# Node_PCB_v20234.net
KiCad netlist of a schematic drawn in EAGLE
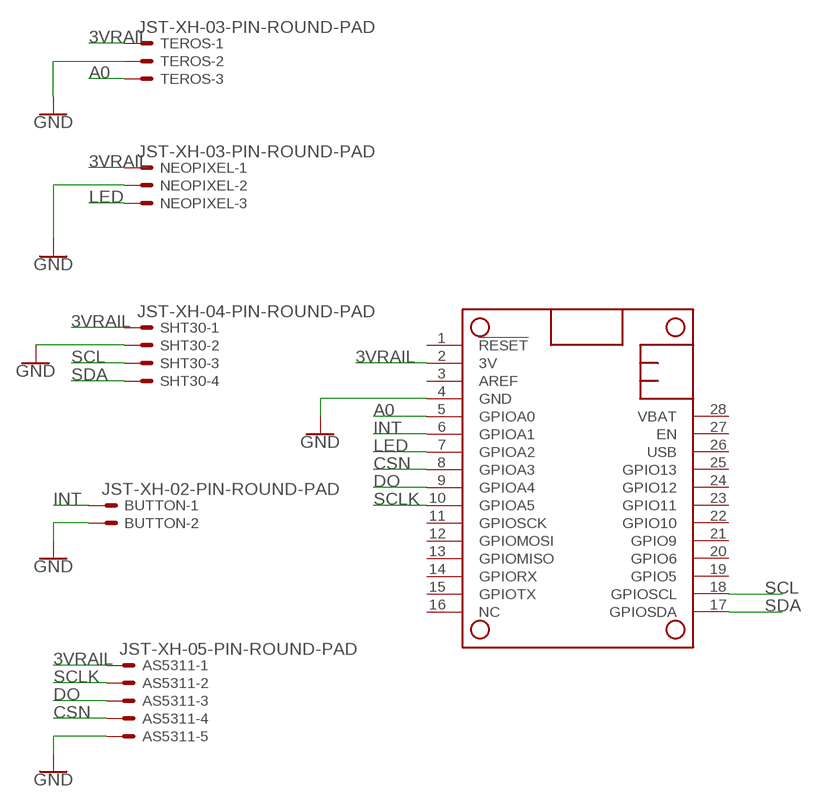
[diagram p0: schematic, sheet 1]

(export (version "E")
  (design (tool "Eeschema 10.0.6"))
  (components
    (comp (ref "AS5311")
      (value "JST-XH-05-PIN-ROUND-PAD")
      (footprint "eagle-import:JST-XH-05-PACKAGE-ROUND-PAD")
      (libsource (lib "eagle-import") (part "JST-XH-05-PIN-ROUND-PAD"))
    )
    (comp (ref "BUTTON")
      (value "JST-XH-02-PIN-ROUND-PAD")
      (footprint "eagle-import:JST-XH-02-PACKAGE-ROUND-PAD")
      (libsource (lib "eagle-import") (part "JST-XH-02-PIN-ROUND-PAD"))
    )
    (comp (ref "MS1")
      (value "FEATHERWING")
      (footprint "eagle-import:FEATHERWING")
      (libsource (lib "eagle-import") (part "FEATHERWING"))
    )
    (comp (ref "NEOPIXEL")
      (value "JST-XH-03-PIN-ROUND-PAD")
      (footprint "eagle-import:JST-XH-03-PACKAGE-ROUND-PAD")
      (libsource (lib "eagle-import") (part "JST-XH-03-PIN-ROUND-PAD"))
    )
    (comp (ref "SHT30")
      (value "JST-XH-04-PIN-ROUND-PAD")
      (footprint "eagle-import:JST-XH-04-PACKAGE-ROUND-PAD")
      (libsource (lib "eagle-import") (part "JST-XH-04-PIN-ROUND-PAD"))
    )
    (comp (ref "TEROS")
      (value "JST-XH-03-PIN-ROUND-PAD")
      (footprint "eagle-import:JST-XH-03-PACKAGE-ROUND-PAD")
      (libsource (lib "eagle-import") (part "JST-XH-03-PIN-ROUND-PAD"))
    )
  )
  (nets
    (net (code "1") (name "/3VRAIL") (class "Default")
      (node (ref "AS5311") (pin "1") (pinfunction "S_1") (pintype "passive"))
      (node (ref "MS1") (pin "2") (pinfunction "3V_2") (pintype "power_in"))
      (node (ref "NEOPIXEL") (pin "1") (pinfunction "S_1") (pintype "passive"))
      (node (ref "SHT30") (pin "1") (pinfunction "S_1") (pintype "passive"))
      (node (ref "TEROS") (pin "1") (pinfunction "S_1") (pintype "passive"))
    )
    (net (code "2") (name "/A0") (class "Default")
      (node (ref "MS1") (pin "5") (pinfunction "GPIOA0_5") (pintype "bidirectional"))
      (node (ref "TEROS") (pin "3") (pinfunction "S_3") (pintype "passive"))
    )
    (net (code "3") (name "/CSN") (class "Default")
      (node (ref "AS5311") (pin "4") (pinfunction "S_4") (pintype "passive"))
      (node (ref "MS1") (pin "8") (pinfunction "GPIOA3_8") (pintype "bidirectional"))
    )
    (net (code "4") (name "/DO") (class "Default")
      (node (ref "AS5311") (pin "3") (pinfunction "S_3") (pintype "passive"))
      (node (ref "MS1") (pin "9") (pinfunction "GPIOA4_9") (pintype "bidirectional"))
    )
    (net (code "5") (name "/INT") (class "Default")
      (node (ref "BUTTON") (pin "1") (pinfunction "S_1") (pintype "passive"))
      (node (ref "MS1") (pin "6") (pinfunction "GPIOA1_6") (pintype "bidirectional"))
    )
    (net (code "6") (name "/LED") (class "Default")
      (node (ref "MS1") (pin "7") (pinfunction "GPIOA2_7") (pintype "bidirectional"))
      (node (ref "NEOPIXEL") (pin "3") (pinfunction "S_3") (pintype "passive"))
    )
    (net (code "7") (name "/SCL") (class "Default")
      (node (ref "MS1") (pin "18") (pinfunction "GPIOSCL_18") (pintype "bidirectional"))
      (node (ref "SHT30") (pin "3") (pinfunction "S_3") (pintype "passive"))
    )
    (net (code "8") (name "/SCLK") (class "Default")
      (node (ref "AS5311") (pin "2") (pinfunction "S_2") (pintype "passive"))
      (node (ref "MS1") (pin "10") (pinfunction "GPIOA5_10") (pintype "bidirectional"))
    )
    (net (code "9") (name "/SDA") (class "Default")
      (node (ref "MS1") (pin "17") (pinfunction "GPIOSDA_17") (pintype "bidirectional"))
      (node (ref "SHT30") (pin "4") (pinfunction "S_4") (pintype "passive"))
    )
    (net (code "10") (name "/USB") (class "Default")
      (node (ref "MS1") (pin "26") (pinfunction "USB_26") (pintype "power_in"))
    )
    (net (code "11") (name "/VBAT") (class "Default")
      (node (ref "MS1") (pin "28") (pinfunction "VBAT_28") (pintype "power_in"))
    )
    (net (code "12") (name "GND") (class "Default")
      (node (ref "AS5311") (pin "5") (pinfunction "S_5") (pintype "passive"))
      (node (ref "BUTTON") (pin "2") (pinfunction "S_2") (pintype "passive"))
      (node (ref "MS1") (pin "4") (pinfunction "GND_4") (pintype "power_in"))
      (node (ref "NEOPIXEL") (pin "2") (pinfunction "S_2") (pintype "passive"))
      (node (ref "SHT30") (pin "2") (pinfunction "S_2") (pintype "passive"))
      (node (ref "TEROS") (pin "2") (pinfunction "S_2") (pintype "passive"))
    )
    (net (code "13") (name "unconnected-(MS1-AREF-Pad3)") (class "Default")
      (node (ref "MS1") (pin "3") (pinfunction "AREF_3") (pintype "passive"))
    )
    (net (code "14") (name "unconnected-(MS1-EN-Pad27)") (class "Default")
      (node (ref "MS1") (pin "27") (pinfunction "EN_27") (pintype "passive"))
    )
    (net (code "15") (name "unconnected-(MS1-GPIO5-Pad19)") (class "Default")
      (node (ref "MS1") (pin "19") (pinfunction "GPIO5_19") (pintype "bidirectional"))
    )
    (net (code "16") (name "unconnected-(MS1-GPIO6-Pad20)") (class "Default")
      (node (ref "MS1") (pin "20") (pinfunction "GPIO6_20") (pintype "bidirectional"))
    )
    (net (code "17") (name "unconnected-(MS1-GPIO9-Pad21)") (class "Default")
      (node (ref "MS1") (pin "21") (pinfunction "GPIO9_21") (pintype "bidirectional"))
    )
    (net (code "18") (name "unconnected-(MS1-GPIO10-Pad22)") (class "Default")
      (node (ref "MS1") (pin "22") (pinfunction "GPIO10_22") (pintype "bidirectional"))
    )
    (net (code "19") (name "unconnected-(MS1-GPIO11-Pad23)") (class "Default")
      (node (ref "MS1") (pin "23") (pinfunction "GPIO11_23") (pintype "bidirectional"))
    )
    (net (code "20") (name "unconnected-(MS1-GPIO12-Pad24)") (class "Default")
      (node (ref "MS1") (pin "24") (pinfunction "GPIO12_24") (pintype "bidirectional"))
    )
    (net (code "21") (name "unconnected-(MS1-GPIO13-Pad25)") (class "Default")
      (node (ref "MS1") (pin "25") (pinfunction "GPIO13_25") (pintype "bidirectional"))
    )
    (net (code "22") (name "unconnected-(MS1-GPIOMISO-Pad13)") (class "Default")
      (node (ref "MS1") (pin "13") (pinfunction "GPIOMISO_13") (pintype "bidirectional"))
    )
    (net (code "23") (name "unconnected-(MS1-GPIOMOSI-Pad12)") (class "Default")
      (node (ref "MS1") (pin "12") (pinfunction "GPIOMOSI_12") (pintype "bidirectional"))
    )
    (net (code "24") (name "unconnected-(MS1-GPIORX-Pad14)") (class "Default")
      (node (ref "MS1") (pin "14") (pinfunction "GPIORX_14") (pintype "bidirectional"))
    )
    (net (code "25") (name "unconnected-(MS1-GPIOSCK-Pad11)") (class "Default")
      (node (ref "MS1") (pin "11") (pinfunction "GPIOSCK_11") (pintype "bidirectional"))
    )
    (net (code "26") (name "unconnected-(MS1-GPIOTX-Pad15)") (class "Default")
      (node (ref "MS1") (pin "15") (pinfunction "GPIOTX_15") (pintype "bidirectional"))
    )
    (net (code "27") (name "unconnected-(MS1-NC-Pad16)") (class "Default")
      (node (ref "MS1") (pin "16") (pinfunction "NC_16") (pintype "passive"))
    )
    (net (code "28") (name "unconnected-(MS1-~{RESET}-Pad1)") (class "Default")
      (node (ref "MS1") (pin "1") (pinfunction "~{RESET}_1") (pintype "input"))
    )
  )
)
